# Power_Supply.net
KiCad netlist of a schematic drawn in Altium Designer
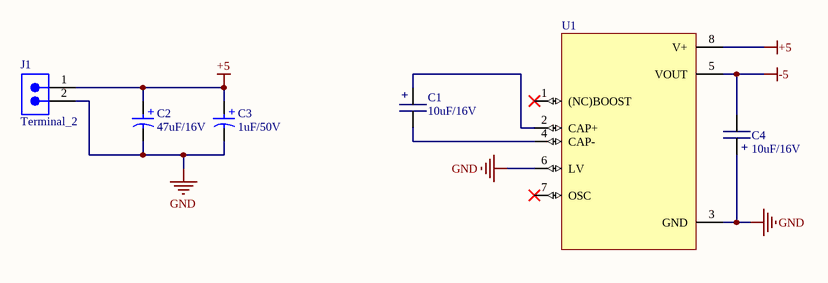
[diagram p0: Power_Supply.SchDoc]

(export (version "E")
  (design (tool "Eeschema 10.0.6"))
  (components
    (comp (ref "C1")
      (value "10uF/16V")
      (footprint "TANTALUM SMD C")
      (libsource (lib "Iot_Flatform_lib_PTT") (part "Capacitor_Polarized_TA"))
    )
    (comp (ref "C2")
      (value "47uF/16V")
      (footprint "WCAP-ASLI_D5H5.5")
      (libsource (lib "Iot_Flatform_lib_PTT") (part "Capacitor_Polarized_AL"))
    )
    (comp (ref "C3")
      (value "1uF/50V")
      (footprint "WCAP-ASLI_D5H5.5")
      (libsource (lib "Iot_Flatform_lib_PTT") (part "Capacitor_Polarized_AL"))
    )
    (comp (ref "C4")
      (value "10uF/16V")
      (footprint "TANTALUM SMD C")
      (libsource (lib "Iot_Flatform_lib_PTT") (part "Capacitor_Polarized_TA"))
    )
    (comp (ref "J1")
      (value "Terminal_2")
      (footprint "TBL_2_3_81")
      (libsource (lib "Iot_Flatform_lib_PTT") (part "Terminal_2"))
    )
    (comp (ref "U1")
      (value "~")
      (footprint "SOIC127P600X175-8N")
      (libsource (lib "Iot_Flatform_lib_PTT") (part "ICL7662CBA-T"))
    )
  )
  (nets
    (net (code "1") (name "+5") (class "Default")
      (node (ref "C2") (pin "1") (pinfunction "P_1") (pintype "passive"))
      (node (ref "C3") (pin "1") (pinfunction "P_1") (pintype "passive"))
      (node (ref "J1") (pin "1") (pinfunction "1_1") (pintype "passive"))
      (node (ref "U1") (pin "8") (pinfunction "V+_8") (pintype "power_in"))
    )
    (net (code "2") (name "-5") (class "Default")
      (node (ref "C4") (pin "1") (pinfunction "1_1") (pintype "passive"))
      (node (ref "U1") (pin "5") (pinfunction "VOUT_5") (pintype "power_in"))
    )
    (net (code "3") (name "GND") (class "Default")
      (node (ref "C2") (pin "2") (pinfunction "N_2") (pintype "passive"))
      (node (ref "C3") (pin "2") (pinfunction "N_2") (pintype "passive"))
      (node (ref "C4") (pin "2") (pinfunction "2_2") (pintype "passive"))
      (node (ref "J1") (pin "2") (pinfunction "2_2") (pintype "passive"))
      (node (ref "U1") (pin "3") (pinfunction "GND_3") (pintype "power_in"))
      (node (ref "U1") (pin "6") (pinfunction "LV_6") (pintype "bidirectional"))
    )
    (net (code "4") (name "Net-(U1-CAP+)") (class "Default")
      (node (ref "C1") (pin "2") (pinfunction "2_2") (pintype "passive"))
      (node (ref "U1") (pin "2") (pinfunction "CAP+_2") (pintype "bidirectional"))
    )
    (net (code "5") (name "Net-(U1-CAP-)") (class "Default")
      (node (ref "C1") (pin "1") (pinfunction "1_1") (pintype "passive"))
      (node (ref "U1") (pin "4") (pinfunction "CAP-_4") (pintype "bidirectional"))
    )
    (net (code "6") (name "unconnected-(U1-(NC)BOOST-Pad1)") (class "Default")
      (node (ref "U1") (pin "1") (pinfunction "(NC)BOOST_1") (pintype "bidirectional+no_connect"))
    )
    (net (code "7") (name "unconnected-(U1-OSC-Pad7)") (class "Default")
      (node (ref "U1") (pin "7") (pinfunction "OSC_7") (pintype "bidirectional+no_connect"))
    )
  )
)
